# pcb_1love.net
KiCad netlist of a schematic drawn in EAGLE
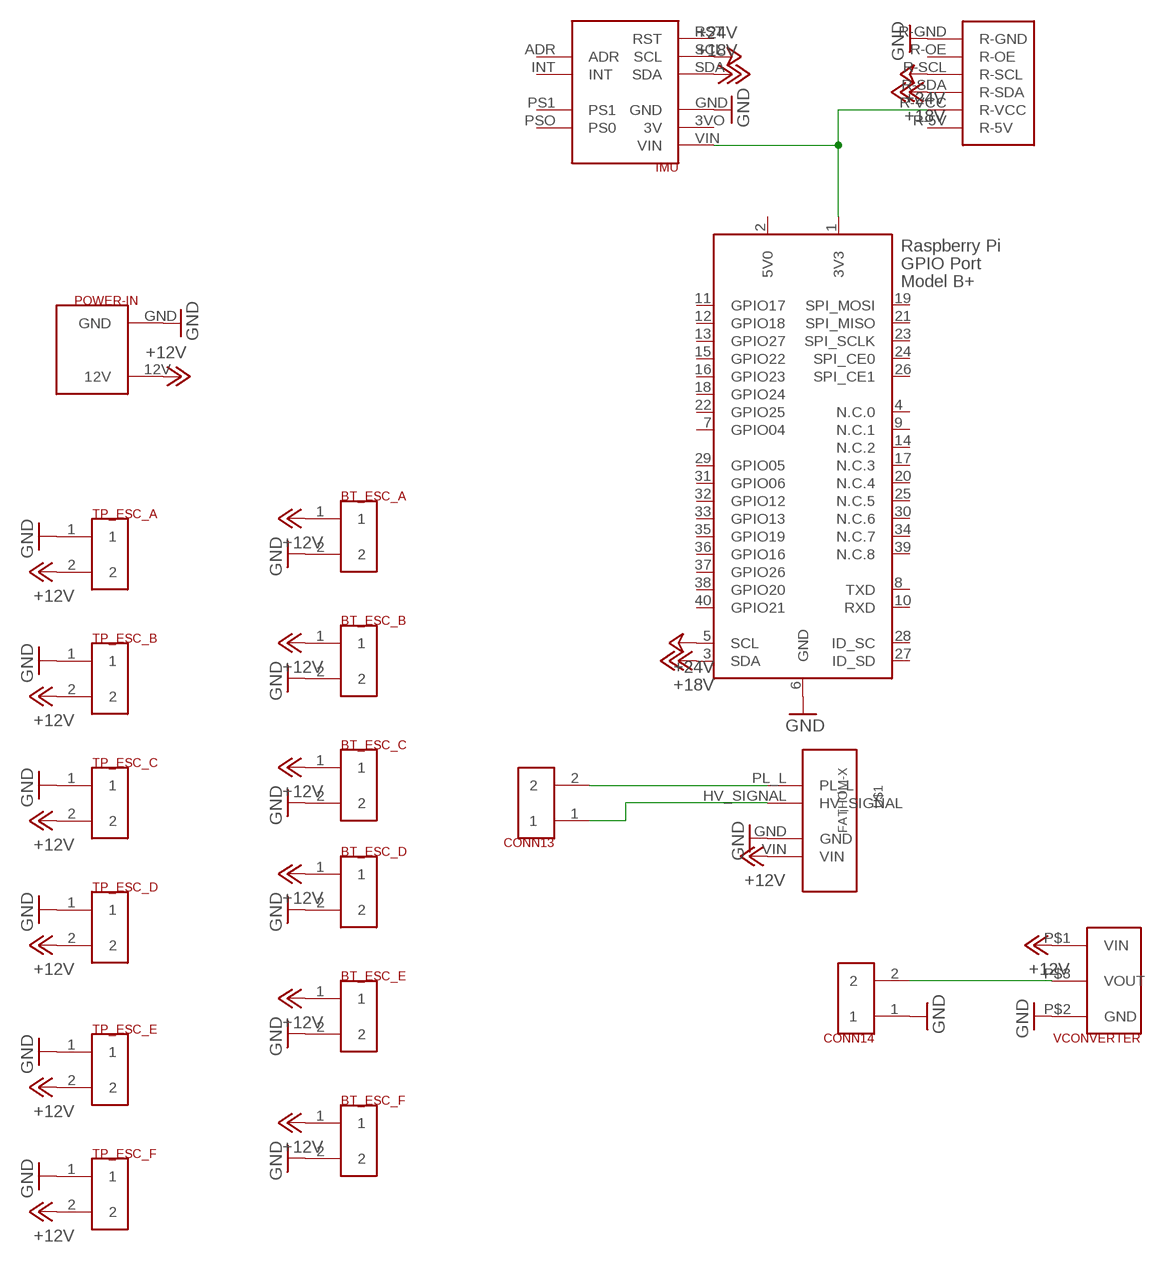
[diagram p0: schematic, sheet 1]

(export (version "E")
  (design (tool "Eeschema 10.0.6"))
  (components
    (comp (ref "BT_ESC_A")
      (value "2CONTACT_ULTRAFIT_R/A")
      (footprint "eagle-import:2CONTAC_ULTRAFIT_R_A")
      (libsource (lib "eagle-import") (part "2CONTACT_ULTRAFIT_R/A"))
    )
    (comp (ref "BT_ESC_B")
      (value "2CONTACT_ULTRAFIT_R/A")
      (footprint "eagle-import:2CONTAC_ULTRAFIT_R_A")
      (libsource (lib "eagle-import") (part "2CONTACT_ULTRAFIT_R/A"))
    )
    (comp (ref "BT_ESC_C")
      (value "2CONTACT_ULTRAFIT_R/A")
      (footprint "eagle-import:2CONTAC_ULTRAFIT_R_A")
      (libsource (lib "eagle-import") (part "2CONTACT_ULTRAFIT_R/A"))
    )
    (comp (ref "BT_ESC_D")
      (value "2CONTACT_ULTRAFIT_R/A")
      (footprint "eagle-import:2CONTAC_ULTRAFIT_R_A")
      (libsource (lib "eagle-import") (part "2CONTACT_ULTRAFIT_R/A"))
    )
    (comp (ref "BT_ESC_E")
      (value "2CONTACT_ULTRAFIT_R/A")
      (footprint "eagle-import:2CONTAC_ULTRAFIT_R_A")
      (libsource (lib "eagle-import") (part "2CONTACT_ULTRAFIT_R/A"))
    )
    (comp (ref "BT_ESC_F")
      (value "2CONTACT_ULTRAFIT_R/A")
      (footprint "eagle-import:2CONTAC_ULTRAFIT_R_A")
      (libsource (lib "eagle-import") (part "2CONTACT_ULTRAFIT_R/A"))
    )
    (comp (ref "CONN13")
      (value "2CONTACT_ULTRAFIT_R/A")
      (footprint "eagle-import:2CONTAC_ULTRAFIT_R_A")
      (libsource (lib "eagle-import") (part "2CONTACT_ULTRAFIT_R/A"))
    )
    (comp (ref "CONN14")
      (value "2CONTACT_ULTRAFIT_R/A")
      (footprint "eagle-import:2CONTAC_ULTRAFIT_R_A")
      (libsource (lib "eagle-import") (part "2CONTACT_ULTRAFIT_R/A"))
    )
    (comp (ref "IMU")
      (value "IMU")
      (footprint "eagle-import:IMU")
      (libsource (lib "eagle-import") (part "IMU"))
    )
    (comp (ref "POWER-IN")
      (value "2-CONTACT-SUPER")
      (footprint "eagle-import:2-CONTACT-SUPER")
      (libsource (lib "eagle-import") (part "2-CONTACT-SUPER"))
    )
    (comp (ref "PWM_EXT")
      (value "PWM_EXTENDER-SIMPLE")
      (footprint "eagle-import:PWM_EXTENDER-SIMPLE")
      (libsource (lib "eagle-import") (part "PWM_EXTENDER-SIMPLE"))
    )
    (comp (ref "TP_ESC_A")
      (value "2CONTACT_ULTRAFIT_R/A")
      (footprint "eagle-import:2CONTAC_ULTRAFIT_R_A")
      (fields (field (name "SPICEPREFIX") "B"))
      (libsource (lib "eagle-import") (part "2CONTACT_ULTRAFIT_R/A"))
    )
    (comp (ref "TP_ESC_B")
      (value "2CONTACT_ULTRAFIT_R/A")
      (footprint "eagle-import:2CONTAC_ULTRAFIT_R_A")
      (libsource (lib "eagle-import") (part "2CONTACT_ULTRAFIT_R/A"))
    )
    (comp (ref "TP_ESC_C")
      (value "2CONTACT_ULTRAFIT_R/A")
      (footprint "eagle-import:2CONTAC_ULTRAFIT_R_A")
      (libsource (lib "eagle-import") (part "2CONTACT_ULTRAFIT_R/A"))
    )
    (comp (ref "TP_ESC_D")
      (value "2CONTACT_ULTRAFIT_R/A")
      (footprint "eagle-import:2CONTAC_ULTRAFIT_R_A")
      (libsource (lib "eagle-import") (part "2CONTACT_ULTRAFIT_R/A"))
    )
    (comp (ref "TP_ESC_E")
      (value "2CONTACT_ULTRAFIT_R/A")
      (footprint "eagle-import:2CONTAC_ULTRAFIT_R_A")
      (libsource (lib "eagle-import") (part "2CONTACT_ULTRAFIT_R/A"))
    )
    (comp (ref "TP_ESC_F")
      (value "2CONTACT_ULTRAFIT_R/A")
      (footprint "eagle-import:2CONTAC_ULTRAFIT_R_A")
      (libsource (lib "eagle-import") (part "2CONTACT_ULTRAFIT_R/A"))
    )
    (comp (ref "U$1")
      (value "FATHOM-X")
      (footprint "eagle-import:FATHOM-X")
      (libsource (lib "eagle-import") (part "FATHOM-X"))
    )
    (comp (ref "VCONVERTER")
      (value "VOLTAGE_CONVERTER")
      (footprint "eagle-import:VOLTAGE_CONVERTERS")
      (libsource (lib "eagle-import") (part "VOLTAGE_CONVERTER"))
    )
    (comp (ref "X1")
      (value "RASPI_BOARD_B+_F")
      (footprint "eagle-import:RASPI_BOARD_B+_FULL")
      (libsource (lib "eagle-import") (part "RASPI_BOARD_B+_F"))
    )
  )
  (nets
    (net (code "1") (name "+12V") (class "Default")
      (node (ref "BT_ESC_A") (pin "1") (pinfunction "1_1") (pintype "bidirectional"))
      (node (ref "BT_ESC_B") (pin "1") (pinfunction "1_1") (pintype "bidirectional"))
      (node (ref "BT_ESC_C") (pin "1") (pinfunction "1_1") (pintype "bidirectional"))
      (node (ref "BT_ESC_D") (pin "1") (pinfunction "1_1") (pintype "bidirectional"))
      (node (ref "BT_ESC_E") (pin "1") (pinfunction "1_1") (pintype "bidirectional"))
      (node (ref "BT_ESC_F") (pin "1") (pinfunction "1_1") (pintype "bidirectional"))
      (node (ref "POWER-IN") (pin "12V") (pinfunction "12V_12V") (pintype "bidirectional"))
      (node (ref "TP_ESC_A") (pin "2") (pinfunction "2_2") (pintype "bidirectional"))
      (node (ref "TP_ESC_B") (pin "2") (pinfunction "2_2") (pintype "bidirectional"))
      (node (ref "TP_ESC_C") (pin "2") (pinfunction "2_2") (pintype "bidirectional"))
      (node (ref "TP_ESC_D") (pin "2") (pinfunction "2_2") (pintype "bidirectional"))
      (node (ref "TP_ESC_E") (pin "2") (pinfunction "2_2") (pintype "bidirectional"))
      (node (ref "TP_ESC_F") (pin "2") (pinfunction "2_2") (pintype "bidirectional"))
      (node (ref "U$1") (pin "VIN") (pinfunction "VIN_VIN") (pintype "bidirectional"))
      (node (ref "VCONVERTER") (pin "P$1") (pinfunction "VIN_P$1") (pintype "bidirectional"))
    )
    (net (code "2") (name "+18V") (class "Default")
      (node (ref "IMU") (pin "SDA") (pinfunction "SDA_SDA") (pintype "bidirectional"))
      (node (ref "PWM_EXT") (pin "R-SDA") (pinfunction "R-SDA_R-SDA") (pintype "bidirectional"))
      (node (ref "X1") (pin "3") (pinfunction "SDA_3") (pintype "bidirectional"))
    )
    (net (code "3") (name "+24V") (class "Default")
      (node (ref "IMU") (pin "SCL") (pinfunction "SCL_SCL") (pintype "bidirectional"))
      (node (ref "PWM_EXT") (pin "R-SCL") (pinfunction "R-SCL_R-SCL") (pintype "bidirectional"))
      (node (ref "X1") (pin "5") (pinfunction "SCL_5") (pintype "bidirectional"))
    )
    (net (code "4") (name "/5V0") (class "Default")
      (node (ref "X1") (pin "2") (pinfunction "5V0_2") (pintype "power_in"))
    )
    (net (code "5") (name "GND") (class "Default")
      (node (ref "BT_ESC_A") (pin "2") (pinfunction "2_2") (pintype "bidirectional"))
      (node (ref "BT_ESC_B") (pin "2") (pinfunction "2_2") (pintype "bidirectional"))
      (node (ref "BT_ESC_C") (pin "2") (pinfunction "2_2") (pintype "bidirectional"))
      (node (ref "BT_ESC_D") (pin "2") (pinfunction "2_2") (pintype "bidirectional"))
      (node (ref "BT_ESC_E") (pin "2") (pinfunction "2_2") (pintype "bidirectional"))
      (node (ref "BT_ESC_F") (pin "2") (pinfunction "2_2") (pintype "bidirectional"))
      (node (ref "CONN14") (pin "1") (pinfunction "1_1") (pintype "bidirectional"))
      (node (ref "IMU") (pin "GND") (pinfunction "GND_GND") (pintype "bidirectional"))
      (node (ref "POWER-IN") (pin "GND") (pinfunction "GND_GND") (pintype "bidirectional"))
      (node (ref "PWM_EXT") (pin "R-GND") (pinfunction "R-GND_R-GND") (pintype "bidirectional"))
      (node (ref "TP_ESC_A") (pin "1") (pinfunction "1_1") (pintype "bidirectional"))
      (node (ref "TP_ESC_B") (pin "1") (pinfunction "1_1") (pintype "bidirectional"))
      (node (ref "TP_ESC_C") (pin "1") (pinfunction "1_1") (pintype "bidirectional"))
      (node (ref "TP_ESC_D") (pin "1") (pinfunction "1_1") (pintype "bidirectional"))
      (node (ref "TP_ESC_E") (pin "1") (pinfunction "1_1") (pintype "bidirectional"))
      (node (ref "TP_ESC_F") (pin "1") (pinfunction "1_1") (pintype "bidirectional"))
      (node (ref "U$1") (pin "GND") (pinfunction "GND_GND") (pintype "bidirectional"))
      (node (ref "VCONVERTER") (pin "P$2") (pinfunction "GND_P$2") (pintype "bidirectional"))
      (node (ref "X1") (pin "6") (pinfunction "GND_6") (pintype "power_in"))
    )
    (net (code "6") (name "Net-(CONN13-Pad1)") (class "Default")
      (node (ref "CONN13") (pin "1") (pinfunction "1_1") (pintype "bidirectional"))
      (node (ref "U$1") (pin "HV_SIGNAL") (pinfunction "HV_SIGNAL_HV_SIGNAL") (pintype "bidirectional"))
    )
    (net (code "7") (name "Net-(CONN13-Pad2)") (class "Default")
      (node (ref "CONN13") (pin "2") (pinfunction "2_2") (pintype "bidirectional"))
      (node (ref "U$1") (pin "PL_L") (pinfunction "PL_L_PL_L") (pintype "bidirectional"))
    )
    (net (code "8") (name "Net-(VCONVERTER-VOUT)") (class "Default")
      (node (ref "CONN14") (pin "2") (pinfunction "2_2") (pintype "bidirectional"))
      (node (ref "VCONVERTER") (pin "P$3") (pinfunction "VOUT_P$3") (pintype "bidirectional"))
    )
    (net (code "9") (name "Net-(X1-3V3)") (class "Default")
      (node (ref "IMU") (pin "VIN") (pinfunction "VIN_VIN") (pintype "bidirectional"))
      (node (ref "PWM_EXT") (pin "R-VCC") (pinfunction "R-VCC_R-VCC") (pintype "bidirectional"))
      (node (ref "X1") (pin "1") (pinfunction "3V3_1") (pintype "power_in"))
    )
    (net (code "10") (name "unconnected-(IMU-3V-Pad3VO)") (class "Default")
      (node (ref "IMU") (pin "3VO") (pinfunction "3V_3VO") (pintype "bidirectional"))
    )
    (net (code "11") (name "unconnected-(IMU-PS0-PadPSO)") (class "Default")
      (node (ref "IMU") (pin "PSO") (pinfunction "PS0_PSO") (pintype "bidirectional"))
    )
    (net (code "12") (name "unconnected-(IMU-PadADR)") (class "Default")
      (node (ref "IMU") (pin "ADR") (pinfunction "ADR_ADR") (pintype "bidirectional"))
    )
    (net (code "13") (name "unconnected-(IMU-PadINT)") (class "Default")
      (node (ref "IMU") (pin "INT") (pinfunction "INT_INT") (pintype "bidirectional"))
    )
    (net (code "14") (name "unconnected-(IMU-PadPS1)") (class "Default")
      (node (ref "IMU") (pin "PS1") (pinfunction "PS1_PS1") (pintype "bidirectional"))
    )
    (net (code "15") (name "unconnected-(IMU-PadRST)") (class "Default")
      (node (ref "IMU") (pin "RST") (pinfunction "RST_RST") (pintype "bidirectional"))
    )
    (net (code "16") (name "unconnected-(PWM_EXT-PadR-5V)") (class "Default")
      (node (ref "PWM_EXT") (pin "R-5V") (pinfunction "R-5V_R-5V") (pintype "bidirectional"))
    )
    (net (code "17") (name "unconnected-(PWM_EXT-PadR-OE)") (class "Default")
      (node (ref "PWM_EXT") (pin "R-OE") (pinfunction "R-OE_R-OE") (pintype "bidirectional"))
    )
    (net (code "18") (name "unconnected-(X1-GPIO04-Pad7)") (class "Default")
      (node (ref "X1") (pin "7") (pinfunction "GPIO04_7") (pintype "bidirectional"))
    )
    (net (code "19") (name "unconnected-(X1-GPIO05-Pad29)") (class "Default")
      (node (ref "X1") (pin "29") (pinfunction "GPIO05_29") (pintype "no_connect"))
    )
    (net (code "20") (name "unconnected-(X1-GPIO06-Pad31)") (class "Default")
      (node (ref "X1") (pin "31") (pinfunction "GPIO06_31") (pintype "no_connect"))
    )
    (net (code "21") (name "unconnected-(X1-GPIO12-Pad32)") (class "Default")
      (node (ref "X1") (pin "32") (pinfunction "GPIO12_32") (pintype "no_connect"))
    )
    (net (code "22") (name "unconnected-(X1-GPIO13-Pad33)") (class "Default")
      (node (ref "X1") (pin "33") (pinfunction "GPIO13_33") (pintype "no_connect"))
    )
    (net (code "23") (name "unconnected-(X1-GPIO16-Pad36)") (class "Default")
      (node (ref "X1") (pin "36") (pinfunction "GPIO16_36") (pintype "no_connect"))
    )
    (net (code "24") (name "unconnected-(X1-GPIO17-Pad11)") (class "Default")
      (node (ref "X1") (pin "11") (pinfunction "GPIO17_11") (pintype "bidirectional"))
    )
    (net (code "25") (name "unconnected-(X1-GPIO18-Pad12)") (class "Default")
      (node (ref "X1") (pin "12") (pinfunction "GPIO18_12") (pintype "bidirectional"))
    )
    (net (code "26") (name "unconnected-(X1-GPIO19-Pad35)") (class "Default")
      (node (ref "X1") (pin "35") (pinfunction "GPIO19_35") (pintype "no_connect"))
    )
    (net (code "27") (name "unconnected-(X1-GPIO20-Pad38)") (class "Default")
      (node (ref "X1") (pin "38") (pinfunction "GPIO20_38") (pintype "no_connect"))
    )
    (net (code "28") (name "unconnected-(X1-GPIO21-Pad40)") (class "Default")
      (node (ref "X1") (pin "40") (pinfunction "GPIO21_40") (pintype "no_connect"))
    )
    (net (code "29") (name "unconnected-(X1-GPIO22-Pad15)") (class "Default")
      (node (ref "X1") (pin "15") (pinfunction "GPIO22_15") (pintype "bidirectional"))
    )
    (net (code "30") (name "unconnected-(X1-GPIO23-Pad16)") (class "Default")
      (node (ref "X1") (pin "16") (pinfunction "GPIO23_16") (pintype "bidirectional"))
    )
    (net (code "31") (name "unconnected-(X1-GPIO24-Pad18)") (class "Default")
      (node (ref "X1") (pin "18") (pinfunction "GPIO24_18") (pintype "bidirectional"))
    )
    (net (code "32") (name "unconnected-(X1-GPIO25-Pad22)") (class "Default")
      (node (ref "X1") (pin "22") (pinfunction "GPIO25_22") (pintype "bidirectional"))
    )
    (net (code "33") (name "unconnected-(X1-GPIO26-Pad37)") (class "Default")
      (node (ref "X1") (pin "37") (pinfunction "GPIO26_37") (pintype "no_connect"))
    )
    (net (code "34") (name "unconnected-(X1-GPIO27-Pad13)") (class "Default")
      (node (ref "X1") (pin "13") (pinfunction "GPIO27_13") (pintype "bidirectional"))
    )
    (net (code "35") (name "unconnected-(X1-ID_SC-Pad28)") (class "Default")
      (node (ref "X1") (pin "28") (pinfunction "ID_SC_28") (pintype "no_connect"))
    )
    (net (code "36") (name "unconnected-(X1-ID_SD-Pad27)") (class "Default")
      (node (ref "X1") (pin "27") (pinfunction "ID_SD_27") (pintype "no_connect"))
    )
    (net (code "37") (name "unconnected-(X1-N.C.0-Pad4)") (class "Default")
      (node (ref "X1") (pin "4") (pinfunction "N.C.0_4") (pintype "no_connect"))
    )
    (net (code "38") (name "unconnected-(X1-N.C.1-Pad9)") (class "Default")
      (node (ref "X1") (pin "9") (pinfunction "N.C.1_9") (pintype "no_connect"))
    )
    (net (code "39") (name "unconnected-(X1-N.C.2-Pad14)") (class "Default")
      (node (ref "X1") (pin "14") (pinfunction "N.C.2_14") (pintype "no_connect"))
    )
    (net (code "40") (name "unconnected-(X1-N.C.3-Pad17)") (class "Default")
      (node (ref "X1") (pin "17") (pinfunction "N.C.3_17") (pintype "no_connect"))
    )
    (net (code "41") (name "unconnected-(X1-N.C.4-Pad20)") (class "Default")
      (node (ref "X1") (pin "20") (pinfunction "N.C.4_20") (pintype "no_connect"))
    )
    (net (code "42") (name "unconnected-(X1-N.C.5-Pad25)") (class "Default")
      (node (ref "X1") (pin "25") (pinfunction "N.C.5_25") (pintype "no_connect"))
    )
    (net (code "43") (name "unconnected-(X1-N.C.6-Pad30)") (class "Default")
      (node (ref "X1") (pin "30") (pinfunction "N.C.6_30") (pintype "no_connect"))
    )
    (net (code "44") (name "unconnected-(X1-N.C.7-Pad34)") (class "Default")
      (node (ref "X1") (pin "34") (pinfunction "N.C.7_34") (pintype "no_connect"))
    )
    (net (code "45") (name "unconnected-(X1-N.C.8-Pad39)") (class "Default")
      (node (ref "X1") (pin "39") (pinfunction "N.C.8_39") (pintype "no_connect"))
    )
    (net (code "46") (name "unconnected-(X1-RXD-Pad10)") (class "Default")
      (node (ref "X1") (pin "10") (pinfunction "RXD_10") (pintype "bidirectional"))
    )
    (net (code "47") (name "unconnected-(X1-SPI_CE0-Pad24)") (class "Default")
      (node (ref "X1") (pin "24") (pinfunction "SPI_CE0_24") (pintype "bidirectional"))
    )
    (net (code "48") (name "unconnected-(X1-SPI_CE1-Pad26)") (class "Default")
      (node (ref "X1") (pin "26") (pinfunction "SPI_CE1_26") (pintype "bidirectional"))
    )
    (net (code "49") (name "unconnected-(X1-SPI_MISO-Pad21)") (class "Default")
      (node (ref "X1") (pin "21") (pinfunction "SPI_MISO_21") (pintype "bidirectional"))
    )
    (net (code "50") (name "unconnected-(X1-SPI_MOSI-Pad19)") (class "Default")
      (node (ref "X1") (pin "19") (pinfunction "SPI_MOSI_19") (pintype "bidirectional"))
    )
    (net (code "51") (name "unconnected-(X1-SPI_SCLK-Pad23)") (class "Default")
      (node (ref "X1") (pin "23") (pinfunction "SPI_SCLK_23") (pintype "bidirectional"))
    )
    (net (code "52") (name "unconnected-(X1-TXD-Pad8)") (class "Default")
      (node (ref "X1") (pin "8") (pinfunction "TXD_8") (pintype "bidirectional"))
    )
  )
)
